# TBA820-Amplifier-3.net
KiCad netlist of a schematic drawn in EAGLE
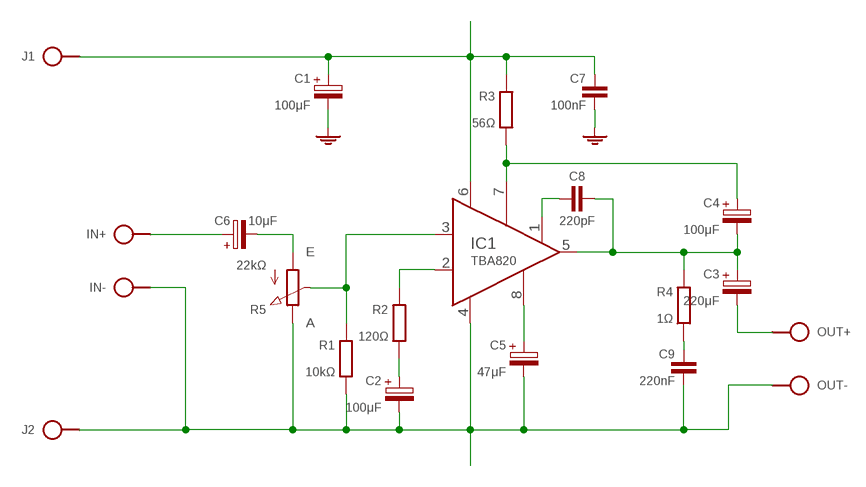
[diagram p0: schematic, sheet 1]

(export (version "E")
  (design (tool "Eeschema 10.0.6"))
  (components
    (comp (ref "C1")
      (value "100μF")
      (footprint "eagle-import:E2.5-4_V")
      (libsource (lib "eagle-import") (part "CPOLE2,5-4/V"))
    )
    (comp (ref "C2")
      (value "100μF")
      (footprint "eagle-import:E2.5-4_V")
      (libsource (lib "eagle-import") (part "CPOLE2,5-4/V"))
    )
    (comp (ref "C3")
      (value "220μF")
      (footprint "eagle-import:E2,5-5")
      (libsource (lib "eagle-import") (part "CPOLE2.5-5"))
    )
    (comp (ref "C4")
      (value "100μF")
      (footprint "eagle-import:E2,5-4")
      (libsource (lib "eagle-import") (part "CPOLE2,5-4"))
    )
    (comp (ref "C5")
      (value "47μF")
      (footprint "eagle-import:E2,5-3")
      (libsource (lib "eagle-import") (part "CPOLE2,5-3"))
    )
    (comp (ref "C6")
      (value "10μF")
      (footprint "eagle-import:E2.5-4_V")
      (libsource (lib "eagle-import") (part "CPOL-HE2,5-4/V"))
    )
    (comp (ref "C7")
      (value "100nF")
      (footprint "eagle-import:C050-020X044_V")
      (libsource (lib "eagle-import") (part "C050-020X044/V"))
    )
    (comp (ref "C8")
      (value "220pF")
      (footprint "eagle-import:C025-015X024")
      (libsource (lib "eagle-import") (part "C-H025-015X024"))
    )
    (comp (ref "C9")
      (value "220nF")
      (footprint "eagle-import:C075-020X044")
      (libsource (lib "eagle-import") (part "C075-020X044"))
    )
    (comp (ref "IC1")
      (value "TBA820")
      (footprint "eagle-import:DIL08")
      (libsource (lib "eagle-import") (part "TBA820"))
    )
    (comp (ref "IN")
      (value "SPAD+--+")
      (footprint "eagle-import:SPAD-+")
      (libsource (lib "eagle-import") (part "SPAD+--+"))
    )
    (comp (ref "J1")
      (value "HPORT")
      (footprint "eagle-import:SPAD")
      (libsource (lib "eagle-import") (part "HPORT"))
    )
    (comp (ref "J2")
      (value "HPORT")
      (footprint "eagle-import:SPAD")
      (libsource (lib "eagle-import") (part "HPORT"))
    )
    (comp (ref "OUT")
      (value "SPAD+-+-")
      (footprint "eagle-import:SPAD+-")
      (libsource (lib "eagle-import") (part "SPAD+-+-"))
    )
    (comp (ref "R1")
      (value "10kΩ")
      (footprint "eagle-import:0204_10-V")
      (libsource (lib "eagle-import") (part "R0204/10-V"))
    )
    (comp (ref "R2")
      (value "120Ω")
      (footprint "eagle-import:0204_10-V")
      (libsource (lib "eagle-import") (part "R0204/10-V"))
    )
    (comp (ref "R3")
      (value "56Ω")
      (footprint "eagle-import:0204_10-V")
      (libsource (lib "eagle-import") (part "R0204/10-V"))
    )
    (comp (ref "R4")
      (value "1Ω")
      (footprint "eagle-import:0204_10-V")
      (libsource (lib "eagle-import") (part "R0204/10-V"))
    )
    (comp (ref "R5")
      (value "22kΩ")
      (footprint "eagle-import:CONN-3P")
      (libsource (lib "eagle-import") (part "POT-3P"))
    )
  )
  (nets
    (net (code "1") (name "GND") (class "Default")
      (node (ref "C1") (pin "-") (pinfunction "-_-") (pintype "passive"))
      (node (ref "C7") (pin "2") (pinfunction "2_2") (pintype "passive"))
    )
    (net (code "2") (name "Net-(IC1-BOOT)") (class "Default")
      (node (ref "C4") (pin "+") (pinfunction "+_+") (pintype "passive"))
      (node (ref "IC1") (pin "7") (pinfunction "BOOT_7") (pintype "input"))
      (node (ref "R3") (pin "2") (pinfunction "1_2") (pintype "passive"))
    )
    (net (code "3") (name "Net-(IC1-FREQ)") (class "Default")
      (node (ref "C8") (pin "1") (pinfunction "1_1") (pintype "passive"))
      (node (ref "IC1") (pin "1") (pinfunction "FREQ_1") (pintype "input"))
    )
    (net (code "4") (name "Net-(IC1-GAIN)") (class "Default")
      (node (ref "IC1") (pin "2") (pinfunction "GAIN_2") (pintype "input"))
      (node (ref "R2") (pin "1") (pinfunction "2_1") (pintype "passive"))
    )
    (net (code "5") (name "Net-(IC1-GND)") (class "Default")
      (node (ref "C2") (pin "-") (pinfunction "-_-") (pintype "passive"))
      (node (ref "C5") (pin "-") (pinfunction "-_-") (pintype "passive"))
      (node (ref "C9") (pin "2") (pinfunction "2_2") (pintype "passive"))
      (node (ref "IC1") (pin "4") (pinfunction "GND_4") (pintype "power_in"))
      (node (ref "IN") (pin "1") (pinfunction "P$1_1") (pintype "passive"))
      (node (ref "J2") (pin "1") (pinfunction "P$1_1") (pintype "passive"))
      (node (ref "OUT") (pin "1") (pinfunction "P$1_1") (pintype "passive"))
      (node (ref "R1") (pin "2") (pinfunction "1_2") (pintype "passive"))
      (node (ref "R5") (pin "3") (pinfunction "E_3") (pintype "passive"))
    )
    (net (code "6") (name "Net-(IC1-INPUT)") (class "Default")
      (node (ref "IC1") (pin "3") (pinfunction "INPUT_3") (pintype "input"))
      (node (ref "R1") (pin "1") (pinfunction "2_1") (pintype "passive"))
      (node (ref "R5") (pin "2") (pinfunction "S_2") (pintype "passive"))
    )
    (net (code "7") (name "Net-(IC1-OUT)") (class "Default")
      (node (ref "C3") (pin "+") (pinfunction "+_+") (pintype "passive"))
      (node (ref "C4") (pin "-") (pinfunction "-_-") (pintype "passive"))
      (node (ref "C8") (pin "2") (pinfunction "2_2") (pintype "passive"))
      (node (ref "IC1") (pin "5") (pinfunction "OUT_5") (pintype "output"))
      (node (ref "R4") (pin "1") (pinfunction "2_1") (pintype "passive"))
    )
    (net (code "8") (name "Net-(IC1-RIPPLE)") (class "Default")
      (node (ref "C5") (pin "+") (pinfunction "+_+") (pintype "passive"))
      (node (ref "IC1") (pin "8") (pinfunction "RIPPLE_8") (pintype "input"))
    )
    (net (code "9") (name "Net-(IC1-VCC)") (class "Default")
      (node (ref "C1") (pin "+") (pinfunction "+_+") (pintype "passive"))
      (node (ref "C7") (pin "1") (pinfunction "1_1") (pintype "passive"))
      (node (ref "IC1") (pin "6") (pinfunction "VCC_6") (pintype "power_in"))
      (node (ref "J1") (pin "1") (pinfunction "P$1_1") (pintype "passive"))
      (node (ref "R3") (pin "1") (pinfunction "2_1") (pintype "passive"))
    )
    (net (code "10") (name "Net-(INA-P$1)") (class "Default")
      (node (ref "C6") (pin "+") (pinfunction "+_+") (pintype "passive"))
      (node (ref "IN") (pin "2") (pinfunction "P$1_2") (pintype "passive"))
    )
    (net (code "11") (name "Net-(OUTA-P$1)") (class "Default")
      (node (ref "C3") (pin "-") (pinfunction "-_-") (pintype "passive"))
      (node (ref "OUT") (pin "2") (pinfunction "P$1_2") (pintype "passive"))
    )
    (net (code "12") (name "Net-(R2-1)") (class "Default")
      (node (ref "C2") (pin "+") (pinfunction "+_+") (pintype "passive"))
      (node (ref "R2") (pin "2") (pinfunction "1_2") (pintype "passive"))
    )
    (net (code "13") (name "Net-(R4-1)") (class "Default")
      (node (ref "C9") (pin "1") (pinfunction "1_1") (pintype "passive"))
      (node (ref "R4") (pin "2") (pinfunction "1_2") (pintype "passive"))
    )
    (net (code "14") (name "Net-(R5-A)") (class "Default")
      (node (ref "C6") (pin "-") (pinfunction "-_-") (pintype "passive"))
      (node (ref "R5") (pin "1") (pinfunction "A_1") (pintype "passive"))
    )
  )
)
